# tinynumitronboard.net
KiCad netlist of a schematic drawn in EAGLE
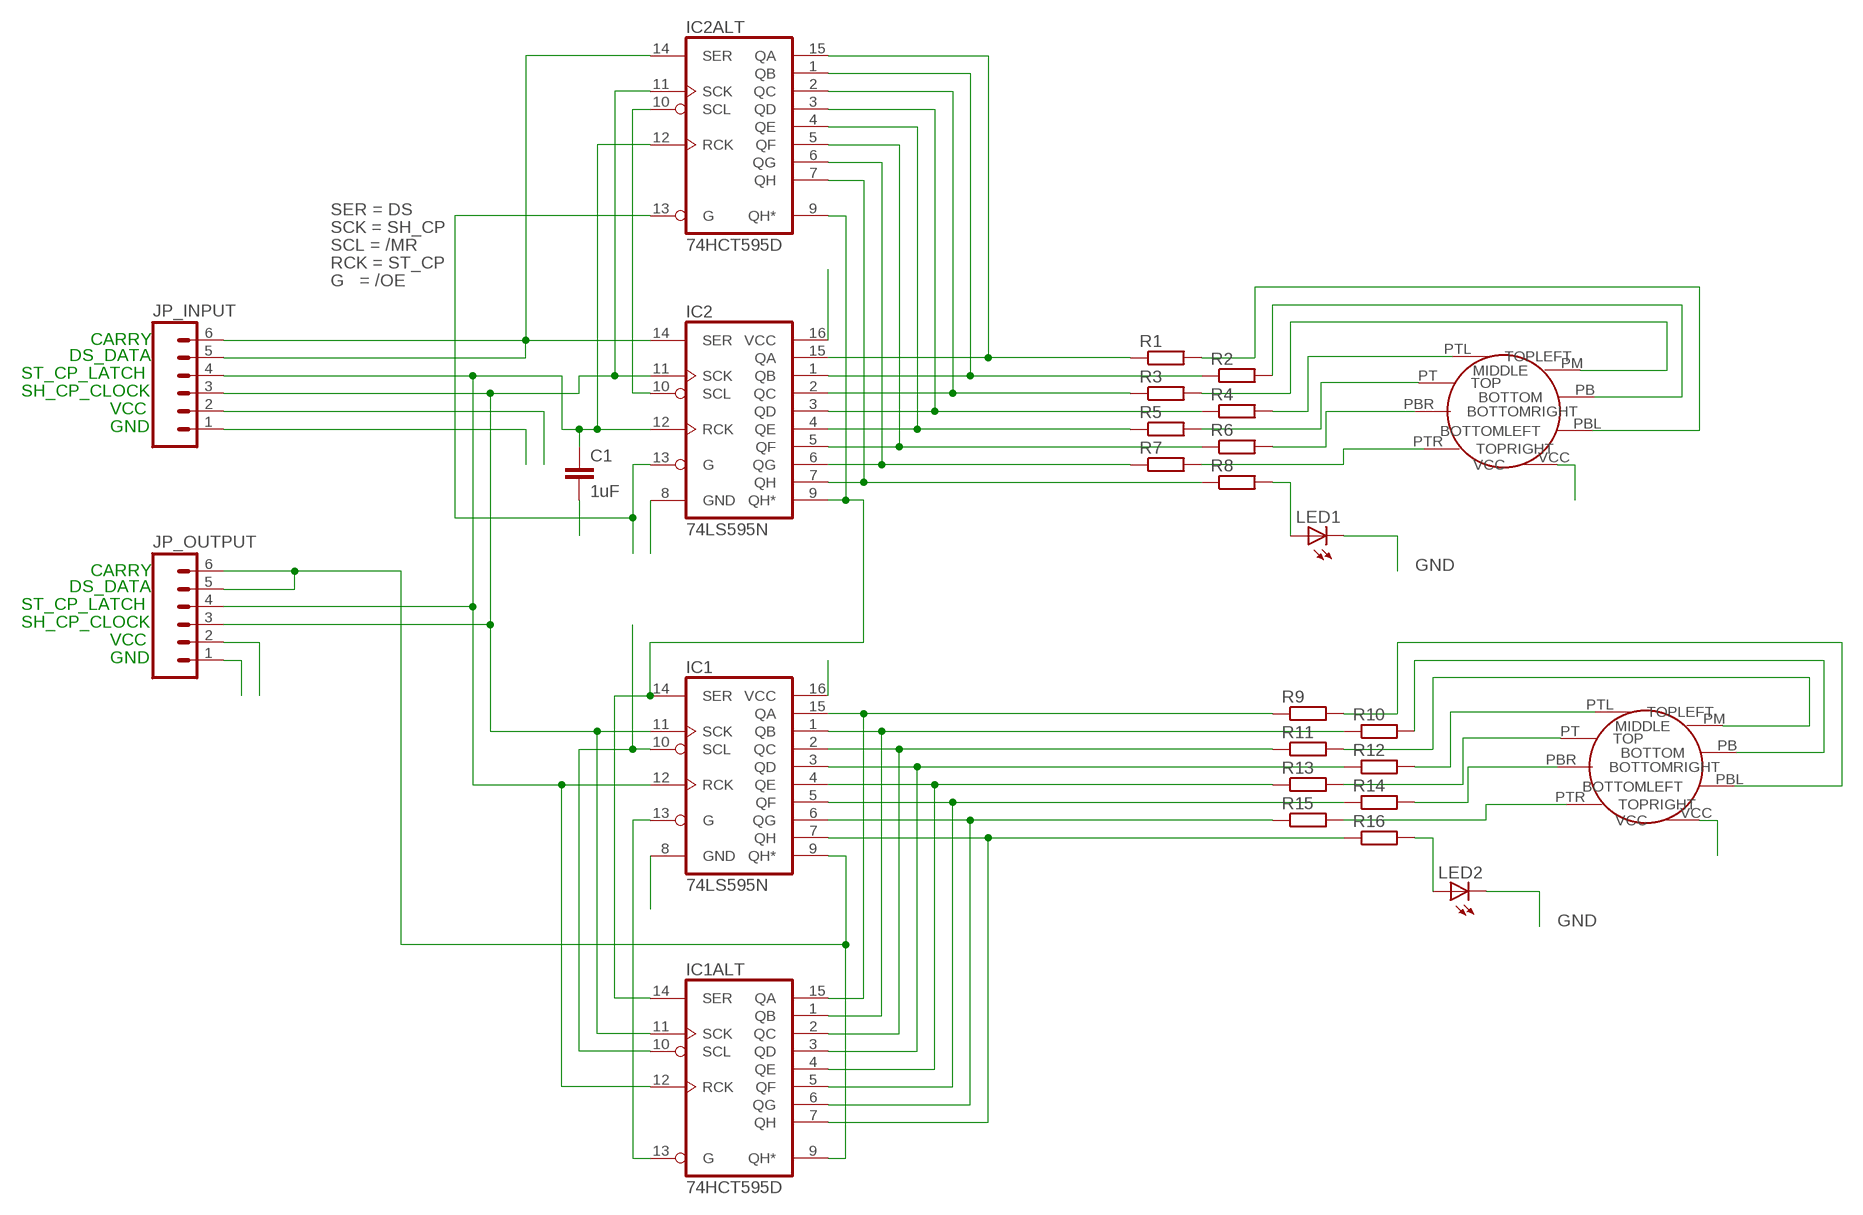
[diagram p0: schematic, sheet 1]

(export (version "E")
  (design (tool "Eeschema 10.0.6"))
  (components
    (comp (ref "C1")
      (value "1uF")
      (footprint "eagle-import:C050-024X044")
      (libsource (lib "eagle-import") (part "C-EU050-024X044"))
    )
    (comp (ref "IC1")
      (value "74LS595N")
      (footprint "eagle-import:DIL16")
      (libsource (lib "eagle-import") (part "SparkFun_74595NLS"))
    )
    (comp (ref "IC1ALT")
      (value "74HCT595D")
      (footprint "eagle-import:SO16")
      (libsource (lib "eagle-import") (part "74595DHCT"))
    )
    (comp (ref "IC2")
      (value "74LS595N")
      (footprint "eagle-import:DIL16")
      (libsource (lib "eagle-import") (part "SparkFun_74595NLS"))
    )
    (comp (ref "IC2ALT")
      (value "74HCT595D")
      (footprint "eagle-import:SO16")
      (libsource (lib "eagle-import") (part "74595DHCT"))
    )
    (comp (ref "JP_INPUT")
      (value "M06SIP")
      (footprint "eagle-import:1X06")
      (libsource (lib "eagle-import") (part "M06SIP"))
    )
    (comp (ref "JP_OUTPUT")
      (value "M06SIP")
      (footprint "eagle-import:1X06")
      (libsource (lib "eagle-import") (part "M06SIP"))
    )
    (comp (ref "LED1")
      (value "LEDKA-3528ASYC")
      (footprint "eagle-import:KA-3528ASYC")
      (libsource (lib "eagle-import") (part "LEDKA-3528ASYC"))
    )
    (comp (ref "LED2")
      (value "LEDKA-3528ASYC")
      (footprint "eagle-import:KA-3528ASYC")
      (libsource (lib "eagle-import") (part "LEDKA-3528ASYC"))
    )
    (comp (ref "R1")
      (value "R-EU_0207/10")
      (footprint "eagle-import:0207_10")
      (libsource (lib "eagle-import") (part "R-EU_0207/10"))
    )
    (comp (ref "R2")
      (value "R-EU_0207/10")
      (footprint "eagle-import:0207_10")
      (libsource (lib "eagle-import") (part "R-EU_0207/10"))
    )
    (comp (ref "R3")
      (value "R-EU_0207/10")
      (footprint "eagle-import:0207_10")
      (libsource (lib "eagle-import") (part "R-EU_0207/10"))
    )
    (comp (ref "R4")
      (value "R-EU_0207/10")
      (footprint "eagle-import:0207_10")
      (libsource (lib "eagle-import") (part "R-EU_0207/10"))
    )
    (comp (ref "R5")
      (value "R-EU_0207/10")
      (footprint "eagle-import:0207_10")
      (libsource (lib "eagle-import") (part "R-EU_0207/10"))
    )
    (comp (ref "R6")
      (value "R-EU_0207/10")
      (footprint "eagle-import:0207_10")
      (libsource (lib "eagle-import") (part "R-EU_0207/10"))
    )
    (comp (ref "R7")
      (value "R-EU_0207/10")
      (footprint "eagle-import:0207_10")
      (libsource (lib "eagle-import") (part "R-EU_0207/10"))
    )
    (comp (ref "R8")
      (value "R-EU_0207/10")
      (footprint "eagle-import:0207_10")
      (libsource (lib "eagle-import") (part "R-EU_0207/10"))
    )
    (comp (ref "R9")
      (value "R-EU_0207/10")
      (footprint "eagle-import:0207_10")
      (libsource (lib "eagle-import") (part "R-EU_0207/10"))
    )
    (comp (ref "R10")
      (value "R-EU_0207/10")
      (footprint "eagle-import:0207_10")
      (libsource (lib "eagle-import") (part "R-EU_0207/10"))
    )
    (comp (ref "R11")
      (value "R-EU_0207/10")
      (footprint "eagle-import:0207_10")
      (libsource (lib "eagle-import") (part "R-EU_0207/10"))
    )
    (comp (ref "R12")
      (value "R-EU_0207/10")
      (footprint "eagle-import:0207_10")
      (libsource (lib "eagle-import") (part "R-EU_0207/10"))
    )
    (comp (ref "R13")
      (value "R-EU_0207/10")
      (footprint "eagle-import:0207_10")
      (libsource (lib "eagle-import") (part "R-EU_0207/10"))
    )
    (comp (ref "R14")
      (value "R-EU_0207/10")
      (footprint "eagle-import:0207_10")
      (libsource (lib "eagle-import") (part "R-EU_0207/10"))
    )
    (comp (ref "R15")
      (value "R-EU_0207/10")
      (footprint "eagle-import:0207_10")
      (libsource (lib "eagle-import") (part "R-EU_0207/10"))
    )
    (comp (ref "R16")
      (value "R-EU_0207/10")
      (footprint "eagle-import:0207_10")
      (libsource (lib "eagle-import") (part "R-EU_0207/10"))
    )
    (comp (ref "U$1")
      (value "IV16TINY_NUMITRON")
      (footprint "eagle-import:IV16TINY_NUMITRON_PAC")
      (libsource (lib "eagle-import") (part "IV16TINY_NUMITRON"))
    )
    (comp (ref "U$2")
      (value "IV16TINY_NUMITRON")
      (footprint "eagle-import:IV16TINY_NUMITRON_PAC")
      (libsource (lib "eagle-import") (part "IV16TINY_NUMITRON"))
    )
  )
  (nets
    (net (code "1") (name "/GND") (class "Default")
      (node (ref "C1") (pin "2") (pinfunction "2_2") (pintype "passive"))
      (node (ref "IC1") (pin "13") (pinfunction "G_13") (pintype "input"))
      (node (ref "IC1") (pin "8") (pinfunction "GND_8") (pintype "power_in"))
      (node (ref "IC1ALT") (pin "13") (pinfunction "G_13") (pintype "input"))
      (node (ref "IC2") (pin "13") (pinfunction "G_13") (pintype "input"))
      (node (ref "IC2") (pin "8") (pinfunction "GND_8") (pintype "power_in"))
      (node (ref "IC2ALT") (pin "13") (pinfunction "G_13") (pintype "input"))
      (node (ref "JP_INPUT") (pin "1") (pinfunction "1_1") (pintype "passive"))
      (node (ref "JP_OUTPUT") (pin "1") (pinfunction "1_1") (pintype "passive"))
      (node (ref "LED1") (pin "C") (pinfunction "C_C") (pintype "passive"))
      (node (ref "LED2") (pin "C") (pinfunction "C_C") (pintype "passive"))
    )
    (net (code "2") (name "/VCC") (class "Default")
      (node (ref "IC1") (pin "10") (pinfunction "SCL_10") (pintype "input"))
      (node (ref "IC1") (pin "16") (pinfunction "VCC_16") (pintype "power_in"))
      (node (ref "IC1ALT") (pin "10") (pinfunction "SCL_10") (pintype "input"))
      (node (ref "IC2") (pin "10") (pinfunction "SCL_10") (pintype "input"))
      (node (ref "IC2") (pin "16") (pinfunction "VCC_16") (pintype "power_in"))
      (node (ref "IC2ALT") (pin "10") (pinfunction "SCL_10") (pintype "input"))
      (node (ref "JP_INPUT") (pin "2") (pinfunction "2_2") (pintype "passive"))
      (node (ref "JP_OUTPUT") (pin "2") (pinfunction "2_2") (pintype "passive"))
      (node (ref "U$1") (pin "VCC") (pinfunction "VCC_VCC") (pintype "input"))
      (node (ref "U$2") (pin "VCC") (pinfunction "VCC_VCC") (pintype "input"))
    )
    (net (code "3") (name "Net-(IC1-QA)") (class "Default")
      (node (ref "IC1") (pin "15") (pinfunction "QA_15") (pintype "tri_state"))
      (node (ref "IC1ALT") (pin "15") (pinfunction "QA_15") (pintype "tri_state"))
      (node (ref "R9") (pin "1") (pinfunction "1_1") (pintype "passive"))
    )
    (net (code "4") (name "Net-(IC1-QB)") (class "Default")
      (node (ref "IC1") (pin "1") (pinfunction "QB_1") (pintype "tri_state"))
      (node (ref "IC1ALT") (pin "1") (pinfunction "QB_1") (pintype "tri_state"))
      (node (ref "R10") (pin "1") (pinfunction "1_1") (pintype "passive"))
    )
    (net (code "5") (name "Net-(IC1-QC)") (class "Default")
      (node (ref "IC1") (pin "2") (pinfunction "QC_2") (pintype "tri_state"))
      (node (ref "IC1ALT") (pin "2") (pinfunction "QC_2") (pintype "tri_state"))
      (node (ref "R11") (pin "1") (pinfunction "1_1") (pintype "passive"))
    )
    (net (code "6") (name "Net-(IC1-QD)") (class "Default")
      (node (ref "IC1") (pin "3") (pinfunction "QD_3") (pintype "tri_state"))
      (node (ref "IC1ALT") (pin "3") (pinfunction "QD_3") (pintype "tri_state"))
      (node (ref "R12") (pin "1") (pinfunction "1_1") (pintype "passive"))
    )
    (net (code "7") (name "Net-(IC1-QE)") (class "Default")
      (node (ref "IC1") (pin "4") (pinfunction "QE_4") (pintype "tri_state"))
      (node (ref "IC1ALT") (pin "4") (pinfunction "QE_4") (pintype "tri_state"))
      (node (ref "R13") (pin "1") (pinfunction "1_1") (pintype "passive"))
    )
    (net (code "8") (name "Net-(IC1-QF)") (class "Default")
      (node (ref "IC1") (pin "5") (pinfunction "QF_5") (pintype "tri_state"))
      (node (ref "IC1ALT") (pin "5") (pinfunction "QF_5") (pintype "tri_state"))
      (node (ref "R14") (pin "1") (pinfunction "1_1") (pintype "passive"))
    )
    (net (code "9") (name "Net-(IC1-QG)") (class "Default")
      (node (ref "IC1") (pin "6") (pinfunction "QG_6") (pintype "tri_state"))
      (node (ref "IC1ALT") (pin "6") (pinfunction "QG_6") (pintype "tri_state"))
      (node (ref "R15") (pin "1") (pinfunction "1_1") (pintype "passive"))
    )
    (net (code "10") (name "Net-(IC1-QH)") (class "Default")
      (node (ref "IC1") (pin "7") (pinfunction "QH_7") (pintype "tri_state"))
      (node (ref "IC1ALT") (pin "7") (pinfunction "QH_7") (pintype "tri_state"))
      (node (ref "R16") (pin "1") (pinfunction "1_1") (pintype "passive"))
    )
    (net (code "11") (name "Net-(IC1-QH*)") (class "Default")
      (node (ref "IC1") (pin "9") (pinfunction "QH*_9") (pintype "tri_state"))
      (node (ref "IC1ALT") (pin "9") (pinfunction "QH*_9") (pintype "tri_state"))
      (node (ref "JP_OUTPUT") (pin "5") (pinfunction "5_5") (pintype "passive"))
      (node (ref "JP_OUTPUT") (pin "6") (pinfunction "6_6") (pintype "passive"))
    )
    (net (code "12") (name "Net-(IC1-RCK)") (class "Default")
      (node (ref "C1") (pin "1") (pinfunction "1_1") (pintype "passive"))
      (node (ref "IC1") (pin "12") (pinfunction "RCK_12") (pintype "input"))
      (node (ref "IC1ALT") (pin "12") (pinfunction "RCK_12") (pintype "input"))
      (node (ref "IC2") (pin "12") (pinfunction "RCK_12") (pintype "input"))
      (node (ref "IC2ALT") (pin "12") (pinfunction "RCK_12") (pintype "input"))
      (node (ref "JP_INPUT") (pin "4") (pinfunction "4_4") (pintype "passive"))
      (node (ref "JP_OUTPUT") (pin "4") (pinfunction "4_4") (pintype "passive"))
    )
    (net (code "13") (name "Net-(IC1-SCK)") (class "Default")
      (node (ref "IC1") (pin "11") (pinfunction "SCK_11") (pintype "input"))
      (node (ref "IC1ALT") (pin "11") (pinfunction "SCK_11") (pintype "input"))
      (node (ref "IC2") (pin "11") (pinfunction "SCK_11") (pintype "input"))
      (node (ref "IC2ALT") (pin "11") (pinfunction "SCK_11") (pintype "input"))
      (node (ref "JP_INPUT") (pin "3") (pinfunction "3_3") (pintype "passive"))
      (node (ref "JP_OUTPUT") (pin "3") (pinfunction "3_3") (pintype "passive"))
    )
    (net (code "14") (name "Net-(IC1-SER)") (class "Default")
      (node (ref "IC1") (pin "14") (pinfunction "SER_14") (pintype "input"))
      (node (ref "IC1ALT") (pin "14") (pinfunction "SER_14") (pintype "input"))
      (node (ref "IC2") (pin "9") (pinfunction "QH*_9") (pintype "tri_state"))
      (node (ref "IC2ALT") (pin "9") (pinfunction "QH*_9") (pintype "tri_state"))
    )
    (net (code "15") (name "Net-(IC2-QA)") (class "Default")
      (node (ref "IC2") (pin "15") (pinfunction "QA_15") (pintype "tri_state"))
      (node (ref "IC2ALT") (pin "15") (pinfunction "QA_15") (pintype "tri_state"))
      (node (ref "R1") (pin "1") (pinfunction "1_1") (pintype "passive"))
    )
    (net (code "16") (name "Net-(IC2-QB)") (class "Default")
      (node (ref "IC2") (pin "1") (pinfunction "QB_1") (pintype "tri_state"))
      (node (ref "IC2ALT") (pin "1") (pinfunction "QB_1") (pintype "tri_state"))
      (node (ref "R2") (pin "1") (pinfunction "1_1") (pintype "passive"))
    )
    (net (code "17") (name "Net-(IC2-QC)") (class "Default")
      (node (ref "IC2") (pin "2") (pinfunction "QC_2") (pintype "tri_state"))
      (node (ref "IC2ALT") (pin "2") (pinfunction "QC_2") (pintype "tri_state"))
      (node (ref "R3") (pin "1") (pinfunction "1_1") (pintype "passive"))
    )
    (net (code "18") (name "Net-(IC2-QD)") (class "Default")
      (node (ref "IC2") (pin "3") (pinfunction "QD_3") (pintype "tri_state"))
      (node (ref "IC2ALT") (pin "3") (pinfunction "QD_3") (pintype "tri_state"))
      (node (ref "R4") (pin "1") (pinfunction "1_1") (pintype "passive"))
    )
    (net (code "19") (name "Net-(IC2-QE)") (class "Default")
      (node (ref "IC2") (pin "4") (pinfunction "QE_4") (pintype "tri_state"))
      (node (ref "IC2ALT") (pin "4") (pinfunction "QE_4") (pintype "tri_state"))
      (node (ref "R5") (pin "1") (pinfunction "1_1") (pintype "passive"))
    )
    (net (code "20") (name "Net-(IC2-QF)") (class "Default")
      (node (ref "IC2") (pin "5") (pinfunction "QF_5") (pintype "tri_state"))
      (node (ref "IC2ALT") (pin "5") (pinfunction "QF_5") (pintype "tri_state"))
      (node (ref "R6") (pin "1") (pinfunction "1_1") (pintype "passive"))
    )
    (net (code "21") (name "Net-(IC2-QG)") (class "Default")
      (node (ref "IC2") (pin "6") (pinfunction "QG_6") (pintype "tri_state"))
      (node (ref "IC2ALT") (pin "6") (pinfunction "QG_6") (pintype "tri_state"))
      (node (ref "R7") (pin "1") (pinfunction "1_1") (pintype "passive"))
    )
    (net (code "22") (name "Net-(IC2-QH)") (class "Default")
      (node (ref "IC2") (pin "7") (pinfunction "QH_7") (pintype "tri_state"))
      (node (ref "IC2ALT") (pin "7") (pinfunction "QH_7") (pintype "tri_state"))
      (node (ref "R8") (pin "1") (pinfunction "1_1") (pintype "passive"))
    )
    (net (code "23") (name "Net-(IC2-SER)") (class "Default")
      (node (ref "IC2") (pin "14") (pinfunction "SER_14") (pintype "input"))
      (node (ref "IC2ALT") (pin "14") (pinfunction "SER_14") (pintype "input"))
      (node (ref "JP_INPUT") (pin "5") (pinfunction "5_5") (pintype "passive"))
      (node (ref "JP_INPUT") (pin "6") (pinfunction "6_6") (pintype "passive"))
    )
    (net (code "24") (name "Net-(LED1-PadA)") (class "Default")
      (node (ref "LED1") (pin "A") (pinfunction "A_A") (pintype "passive"))
      (node (ref "R8") (pin "2") (pinfunction "2_2") (pintype "passive"))
    )
    (net (code "25") (name "Net-(LED2-PadA)") (class "Default")
      (node (ref "LED2") (pin "A") (pinfunction "A_A") (pintype "passive"))
      (node (ref "R16") (pin "2") (pinfunction "2_2") (pintype "passive"))
    )
    (net (code "26") (name "Net-(U$1-BOTTOM)") (class "Default")
      (node (ref "R2") (pin "2") (pinfunction "2_2") (pintype "passive"))
      (node (ref "U$1") (pin "PB") (pinfunction "BOTTOM_PB") (pintype "input"))
    )
    (net (code "27") (name "Net-(U$1-BOTTOMLEFT)") (class "Default")
      (node (ref "R1") (pin "2") (pinfunction "2_2") (pintype "passive"))
      (node (ref "U$1") (pin "PBL") (pinfunction "BOTTOMLEFT_PBL") (pintype "input"))
    )
    (net (code "28") (name "Net-(U$1-BOTTOMRIGHT)") (class "Default")
      (node (ref "R6") (pin "2") (pinfunction "2_2") (pintype "passive"))
      (node (ref "U$1") (pin "PBR") (pinfunction "BOTTOMRIGHT_PBR") (pintype "input"))
    )
    (net (code "29") (name "Net-(U$1-MIDDLE)") (class "Default")
      (node (ref "R3") (pin "2") (pinfunction "2_2") (pintype "passive"))
      (node (ref "U$1") (pin "PM") (pinfunction "MIDDLE_PM") (pintype "input"))
    )
    (net (code "30") (name "Net-(U$1-TOP)") (class "Default")
      (node (ref "R5") (pin "2") (pinfunction "2_2") (pintype "passive"))
      (node (ref "U$1") (pin "PT") (pinfunction "TOP_PT") (pintype "input"))
    )
    (net (code "31") (name "Net-(U$1-TOPLEFT)") (class "Default")
      (node (ref "R4") (pin "2") (pinfunction "2_2") (pintype "passive"))
      (node (ref "U$1") (pin "PTL") (pinfunction "TOPLEFT_PTL") (pintype "input"))
    )
    (net (code "32") (name "Net-(U$1-TOPRIGHT)") (class "Default")
      (node (ref "R7") (pin "2") (pinfunction "2_2") (pintype "passive"))
      (node (ref "U$1") (pin "PTR") (pinfunction "TOPRIGHT_PTR") (pintype "input"))
    )
    (net (code "33") (name "Net-(U$2-BOTTOM)") (class "Default")
      (node (ref "R10") (pin "2") (pinfunction "2_2") (pintype "passive"))
      (node (ref "U$2") (pin "PB") (pinfunction "BOTTOM_PB") (pintype "input"))
    )
    (net (code "34") (name "Net-(U$2-BOTTOMLEFT)") (class "Default")
      (node (ref "R9") (pin "2") (pinfunction "2_2") (pintype "passive"))
      (node (ref "U$2") (pin "PBL") (pinfunction "BOTTOMLEFT_PBL") (pintype "input"))
    )
    (net (code "35") (name "Net-(U$2-BOTTOMRIGHT)") (class "Default")
      (node (ref "R14") (pin "2") (pinfunction "2_2") (pintype "passive"))
      (node (ref "U$2") (pin "PBR") (pinfunction "BOTTOMRIGHT_PBR") (pintype "input"))
    )
    (net (code "36") (name "Net-(U$2-MIDDLE)") (class "Default")
      (node (ref "R11") (pin "2") (pinfunction "2_2") (pintype "passive"))
      (node (ref "U$2") (pin "PM") (pinfunction "MIDDLE_PM") (pintype "input"))
    )
    (net (code "37") (name "Net-(U$2-TOP)") (class "Default")
      (node (ref "R13") (pin "2") (pinfunction "2_2") (pintype "passive"))
      (node (ref "U$2") (pin "PT") (pinfunction "TOP_PT") (pintype "input"))
    )
    (net (code "38") (name "Net-(U$2-TOPLEFT)") (class "Default")
      (node (ref "R12") (pin "2") (pinfunction "2_2") (pintype "passive"))
      (node (ref "U$2") (pin "PTL") (pinfunction "TOPLEFT_PTL") (pintype "input"))
    )
    (net (code "39") (name "Net-(U$2-TOPRIGHT)") (class "Default")
      (node (ref "R15") (pin "2") (pinfunction "2_2") (pintype "passive"))
      (node (ref "U$2") (pin "PTR") (pinfunction "TOPRIGHT_PTR") (pintype "input"))
    )
  )
)
